# Schematic.net
KiCad netlist of a schematic drawn in EAGLE
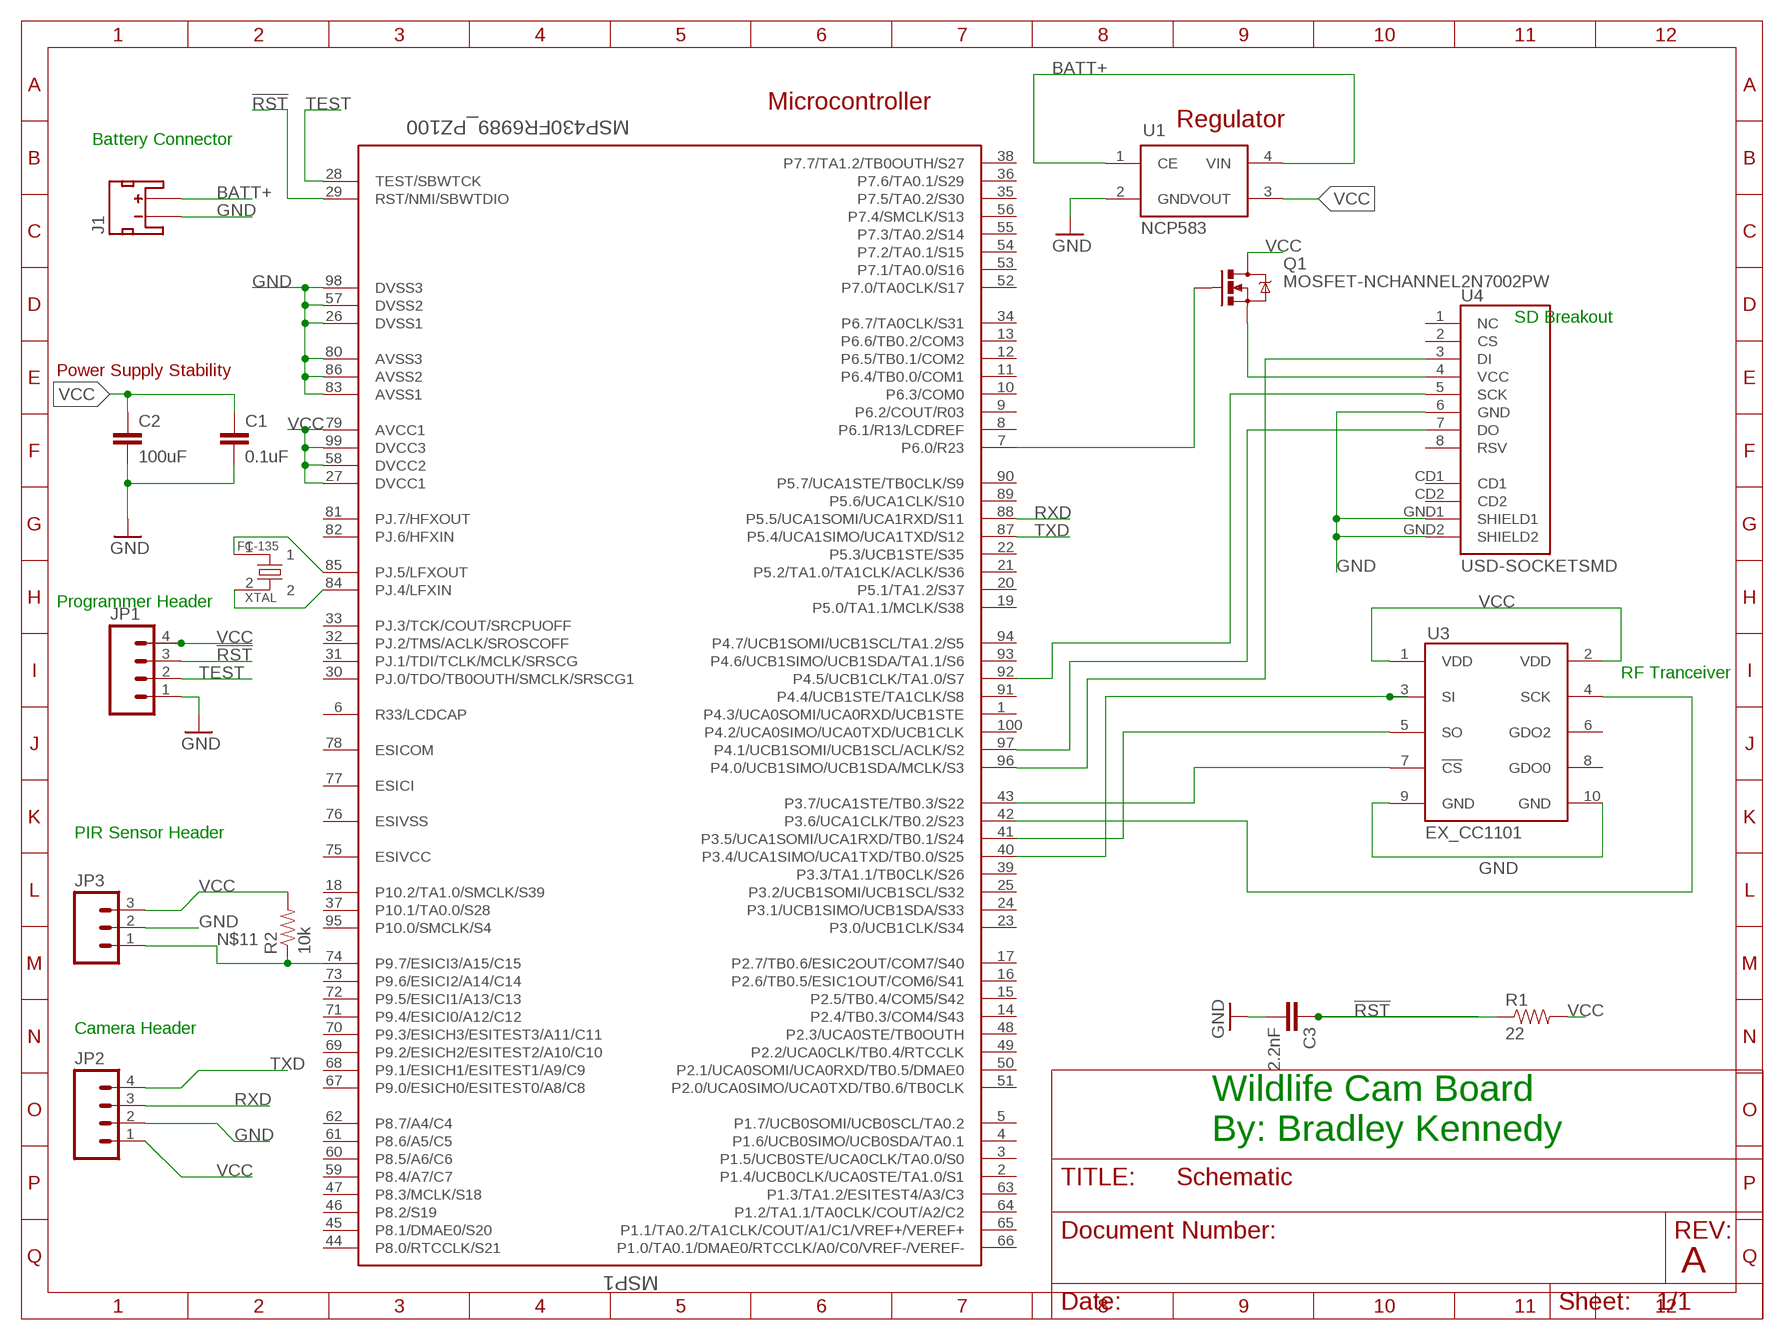
[diagram p0: schematic, sheet 1]

(export (version "E")
  (design (tool "Eeschema 10.0.6"))
  (components
    (comp (ref "C1")
      (value "0.1uF")
      (footprint "eagle-import:0805")
      (libsource (lib "eagle-import") (part "1.0UF-25V-+80/-20(0805)"))
    )
    (comp (ref "C2")
      (value "100uF")
      (footprint "eagle-import:0805")
      (libsource (lib "eagle-import") (part "1.0UF-25V-+80/-20(0805)"))
    )
    (comp (ref "C3")
      (value "2.2nF")
      (footprint "eagle-import:0805")
      (libsource (lib "eagle-import") (part "1.0UF-25V-+80/-20(0805)"))
    )
    (comp (ref "J1")
      (value "JST_2MM_MALE")
      (footprint "eagle-import:JST-2-SMD")
      (libsource (lib "eagle-import") (part "JST_2MM_MALE"))
    )
    (comp (ref "JP1")
      (value "M04PTH")
      (footprint "eagle-import:1X04")
      (libsource (lib "eagle-import") (part "M04PTH"))
    )
    (comp (ref "JP2")
      (value "M04PTH")
      (footprint "eagle-import:1X04")
      (libsource (lib "eagle-import") (part "M04PTH"))
    )
    (comp (ref "JP3")
      (value "M03PTH")
      (footprint "eagle-import:1X03")
      (libsource (lib "eagle-import") (part "M03PTH"))
    )
    (comp (ref "MSP1")
      (value "MSP430FR6989_PZ100")
      (footprint "eagle-import:PZ100")
      (libsource (lib "eagle-import") (part "MSP430FR6989_PZ100"))
    )
    (comp (ref "Q1")
      (value "MOSFET-NCHANNEL2N7002PW")
      (footprint "eagle-import:SOT323")
      (libsource (lib "eagle-import") (part "MOSFET-NCHANNEL2N7002PW"))
    )
    (comp (ref "R1")
      (value "22")
      (footprint "eagle-import:0603-RES")
      (libsource (lib "eagle-import") (part "22OHM1/10W1%(0603)"))
    )
    (comp (ref "R2")
      (value "10k")
      (footprint "eagle-import:AXIAL-0.3EZ")
      (libsource (lib "eagle-import") (part "10KOHM-1/4W-1%(PTH)HORIZ-KIT"))
    )
    (comp (ref "U1")
      (value "NCP583")
      (footprint "eagle-import:SC82-AB_1PRIMARY")
      (libsource (lib "eagle-import") (part "NCP583"))
    )
    (comp (ref "U3")
      (value "EX_CC1101")
      (footprint "eagle-import:2X5")
      (libsource (lib "eagle-import") (part "EX_CC1101"))
    )
    (comp (ref "U4")
      (value "USD-SOCKETSMD")
      (footprint "eagle-import:MICRO-SD-SOCKET-PP")
      (libsource (lib "eagle-import") (part "USD-SOCKETSMD"))
    )
    (comp (ref "XTAL")
      (value "FC-135")
      (footprint "eagle-import:FC-135_1PRIMARY")
      (libsource (lib "eagle-import") (part "FC-135"))
    )
  )
  (nets
    (net (code "1") (name "/BATT+") (class "Default")
      (node (ref "J1") (pin "2") (pinfunction "+_2") (pintype "bidirectional"))
      (node (ref "U1") (pin "1") (pinfunction "CE_1") (pintype "bidirectional"))
      (node (ref "U1") (pin "4") (pinfunction "VIN_4") (pintype "bidirectional"))
    )
    (net (code "2") (name "/N$11") (class "Default")
      (node (ref "JP3") (pin "1") (pinfunction "1_1") (pintype "passive"))
      (node (ref "MSP1") (pin "74") (pinfunction "P9.7/ESICI3/A15/C15_74") (pintype "bidirectional"))
      (node (ref "R2") (pin "P$1") (pinfunction "1_P$1") (pintype "passive"))
    )
    (net (code "3") (name "/RXD") (class "Default")
      (node (ref "JP2") (pin "3") (pinfunction "3_3") (pintype "passive"))
      (node (ref "MSP1") (pin "88") (pinfunction "P5.5/UCA1SOMI/UCA1RXD/S11_88") (pintype "bidirectional"))
    )
    (net (code "4") (name "/TEST") (class "Default")
      (node (ref "JP1") (pin "2") (pinfunction "2_2") (pintype "passive"))
      (node (ref "MSP1") (pin "28") (pinfunction "TEST/SBWTCK_28") (pintype "bidirectional"))
    )
    (net (code "5") (name "/TXD") (class "Default")
      (node (ref "JP2") (pin "4") (pinfunction "4_4") (pintype "passive"))
      (node (ref "MSP1") (pin "87") (pinfunction "P5.4/UCA1SIMO/UCA1TXD/S12_87") (pintype "bidirectional"))
    )
    (net (code "6") (name "/~{RST}") (class "Default")
      (node (ref "C3") (pin "1") (pinfunction "1_1") (pintype "passive"))
      (node (ref "JP1") (pin "3") (pinfunction "3_3") (pintype "passive"))
      (node (ref "MSP1") (pin "29") (pinfunction "RST/NMI/SBWTDIO_29") (pintype "bidirectional"))
      (node (ref "R1") (pin "1") (pinfunction "1_1") (pintype "passive"))
    )
    (net (code "7") (name "GND") (class "Default")
      (node (ref "C1") (pin "2") (pinfunction "2_2") (pintype "passive"))
      (node (ref "C2") (pin "2") (pinfunction "2_2") (pintype "passive"))
      (node (ref "C3") (pin "2") (pinfunction "2_2") (pintype "passive"))
      (node (ref "J1") (pin "1") (pinfunction "-_1") (pintype "bidirectional"))
      (node (ref "JP1") (pin "1") (pinfunction "1_1") (pintype "passive"))
      (node (ref "JP2") (pin "2") (pinfunction "2_2") (pintype "passive"))
      (node (ref "JP3") (pin "2") (pinfunction "2_2") (pintype "passive"))
      (node (ref "MSP1") (pin "26") (pinfunction "DVSS1_26") (pintype "bidirectional"))
      (node (ref "MSP1") (pin "57") (pinfunction "DVSS2_57") (pintype "bidirectional"))
      (node (ref "MSP1") (pin "80") (pinfunction "AVSS3_80") (pintype "bidirectional"))
      (node (ref "MSP1") (pin "83") (pinfunction "AVSS1_83") (pintype "bidirectional"))
      (node (ref "MSP1") (pin "86") (pinfunction "AVSS2_86") (pintype "bidirectional"))
      (node (ref "MSP1") (pin "98") (pinfunction "DVSS3_98") (pintype "bidirectional"))
      (node (ref "U1") (pin "2") (pinfunction "GND_2") (pintype "bidirectional"))
      (node (ref "U3") (pin "10") (pinfunction "GND_10") (pintype "bidirectional"))
      (node (ref "U3") (pin "9") (pinfunction "GND_9") (pintype "bidirectional"))
      (node (ref "U4") (pin "6") (pinfunction "GND_6") (pintype "bidirectional"))
      (node (ref "U4") (pin "GND1") (pinfunction "SHIELD1_GND1") (pintype "bidirectional"))
      (node (ref "U4") (pin "GND2") (pinfunction "SHIELD2_GND2") (pintype "bidirectional"))
    )
    (net (code "8") (name "Net-(MSP1-P3.4{slash}UCA1SIMO{slash}UCA1TXD{slash}TB0.0{slash}S25)") (class "Default")
      (node (ref "MSP1") (pin "40") (pinfunction "P3.4/UCA1SIMO/UCA1TXD/TB0.0/S25_40") (pintype "bidirectional"))
      (node (ref "U3") (pin "3") (pinfunction "SI_3") (pintype "bidirectional"))
    )
    (net (code "9") (name "Net-(MSP1-P3.5{slash}UCA1SOMI{slash}UCA1RXD{slash}TB0.1{slash}S24)") (class "Default")
      (node (ref "MSP1") (pin "41") (pinfunction "P3.5/UCA1SOMI/UCA1RXD/TB0.1/S24_41") (pintype "bidirectional"))
      (node (ref "U3") (pin "5") (pinfunction "SO_5") (pintype "bidirectional"))
    )
    (net (code "10") (name "Net-(MSP1-P3.6{slash}UCA1CLK{slash}TB0.2{slash}S23)") (class "Default")
      (node (ref "MSP1") (pin "42") (pinfunction "P3.6/UCA1CLK/TB0.2/S23_42") (pintype "bidirectional"))
      (node (ref "U3") (pin "4") (pinfunction "SCK_4") (pintype "bidirectional"))
    )
    (net (code "11") (name "Net-(MSP1-P3.7{slash}UCA1STE{slash}TB0.3{slash}S22)") (class "Default")
      (node (ref "MSP1") (pin "43") (pinfunction "P3.7/UCA1STE/TB0.3/S22_43") (pintype "bidirectional"))
      (node (ref "U3") (pin "7") (pinfunction "~{CS}_7") (pintype "bidirectional"))
    )
    (net (code "12") (name "Net-(MSP1-P4.0{slash}UCB1SIMO{slash}UCB1SDA{slash}MCLK{slash}S3)") (class "Default")
      (node (ref "MSP1") (pin "96") (pinfunction "P4.0/UCB1SIMO/UCB1SDA/MCLK/S3_96") (pintype "bidirectional"))
      (node (ref "U4") (pin "3") (pinfunction "DI_3") (pintype "bidirectional"))
    )
    (net (code "13") (name "Net-(MSP1-P4.1{slash}UCB1SOMI{slash}UCB1SCL{slash}ACLK{slash}S2)") (class "Default")
      (node (ref "MSP1") (pin "97") (pinfunction "P4.1/UCB1SOMI/UCB1SCL/ACLK/S2_97") (pintype "bidirectional"))
      (node (ref "U4") (pin "7") (pinfunction "DO_7") (pintype "bidirectional"))
    )
    (net (code "14") (name "Net-(MSP1-P4.5{slash}UCB1CLK{slash}TA1.0{slash}S7)") (class "Default")
      (node (ref "MSP1") (pin "92") (pinfunction "P4.5/UCB1CLK/TA1.0/S7_92") (pintype "bidirectional"))
      (node (ref "U4") (pin "5") (pinfunction "SCK_5") (pintype "bidirectional"))
    )
    (net (code "15") (name "Net-(MSP1-P6.0{slash}R23)") (class "Default")
      (node (ref "MSP1") (pin "7") (pinfunction "P6.0/R23_7") (pintype "bidirectional"))
      (node (ref "Q1") (pin "1") (pinfunction "G_1") (pintype "passive"))
    )
    (net (code "16") (name "Net-(MSP1-PJ.4{slash}LFXIN)") (class "Default")
      (node (ref "MSP1") (pin "84") (pinfunction "PJ.4/LFXIN_84") (pintype "bidirectional"))
      (node (ref "XTAL") (pin "2") (pinfunction "2_2") (pintype "bidirectional"))
    )
    (net (code "17") (name "Net-(MSP1-PJ.5{slash}LFXOUT)") (class "Default")
      (node (ref "MSP1") (pin "85") (pinfunction "PJ.5/LFXOUT_85") (pintype "bidirectional"))
      (node (ref "XTAL") (pin "1") (pinfunction "1_1") (pintype "bidirectional"))
    )
    (net (code "18") (name "Net-(Q1-S)") (class "Default")
      (node (ref "Q1") (pin "2") (pinfunction "S_2") (pintype "passive"))
      (node (ref "U4") (pin "4") (pinfunction "VCC_4") (pintype "bidirectional"))
    )
    (net (code "19") (name "VCC") (class "Default")
      (node (ref "C1") (pin "1") (pinfunction "1_1") (pintype "passive"))
      (node (ref "C2") (pin "1") (pinfunction "1_1") (pintype "passive"))
      (node (ref "JP1") (pin "4") (pinfunction "4_4") (pintype "passive"))
      (node (ref "JP2") (pin "1") (pinfunction "1_1") (pintype "passive"))
      (node (ref "JP3") (pin "3") (pinfunction "3_3") (pintype "passive"))
      (node (ref "MSP1") (pin "27") (pinfunction "DVCC1_27") (pintype "bidirectional"))
      (node (ref "MSP1") (pin "58") (pinfunction "DVCC2_58") (pintype "bidirectional"))
      (node (ref "MSP1") (pin "79") (pinfunction "AVCC1_79") (pintype "bidirectional"))
      (node (ref "MSP1") (pin "99") (pinfunction "DVCC3_99") (pintype "bidirectional"))
      (node (ref "Q1") (pin "3") (pinfunction "D_3") (pintype "passive"))
      (node (ref "R1") (pin "2") (pinfunction "2_2") (pintype "passive"))
      (node (ref "R2") (pin "P$2") (pinfunction "2_P$2") (pintype "passive"))
      (node (ref "U1") (pin "3") (pinfunction "VOUT_3") (pintype "bidirectional"))
      (node (ref "U3") (pin "1") (pinfunction "VDD_1") (pintype "bidirectional"))
      (node (ref "U3") (pin "2") (pinfunction "VDD_2") (pintype "bidirectional"))
    )
    (net (code "20") (name "unconnected-(J1-PAD1-PadNC1)") (class "Default")
      (node (ref "J1") (pin "NC1") (pinfunction "PAD1_NC1") (pintype "bidirectional"))
    )
    (net (code "21") (name "unconnected-(J1-PAD2-PadNC2)") (class "Default")
      (node (ref "J1") (pin "NC2") (pinfunction "PAD2_NC2") (pintype "bidirectional"))
    )
    (net (code "22") (name "unconnected-(MSP1-ESICI-Pad77)") (class "Default")
      (node (ref "MSP1") (pin "77") (pinfunction "ESICI_77") (pintype "bidirectional"))
    )
    (net (code "23") (name "unconnected-(MSP1-ESICOM-Pad78)") (class "Default")
      (node (ref "MSP1") (pin "78") (pinfunction "ESICOM_78") (pintype "bidirectional"))
    )
    (net (code "24") (name "unconnected-(MSP1-ESIVCC-Pad75)") (class "Default")
      (node (ref "MSP1") (pin "75") (pinfunction "ESIVCC_75") (pintype "bidirectional"))
    )
    (net (code "25") (name "unconnected-(MSP1-ESIVSS-Pad76)") (class "Default")
      (node (ref "MSP1") (pin "76") (pinfunction "ESIVSS_76") (pintype "bidirectional"))
    )
    (net (code "26") (name "unconnected-(MSP1-P1.0{slash}TA0.1{slash}DMAE0{slash}RTCCLK{slash}A0{slash}C0{slash}VREF-{slash}VEREF--Pad66)") (class "Default")
      (node (ref "MSP1") (pin "66") (pinfunction "P1.0/TA0.1/DMAE0/RTCCLK/A0/C0/VREF-/VEREF-_66") (pintype "bidirectional"))
    )
    (net (code "27") (name "unconnected-(MSP1-P1.1{slash}TA0.2{slash}TA1CLK{slash}COUT{slash}A1{slash}C1{slash}VREF+{slash}VEREF+-Pad65)") (class "Default")
      (node (ref "MSP1") (pin "65") (pinfunction "P1.1/TA0.2/TA1CLK/COUT/A1/C1/VREF+/VEREF+_65") (pintype "bidirectional"))
    )
    (net (code "28") (name "unconnected-(MSP1-P1.2{slash}TA1.1{slash}TA0CLK{slash}COUT{slash}A2{slash}C2-Pad64)") (class "Default")
      (node (ref "MSP1") (pin "64") (pinfunction "P1.2/TA1.1/TA0CLK/COUT/A2/C2_64") (pintype "bidirectional"))
    )
    (net (code "29") (name "unconnected-(MSP1-P1.3{slash}TA1.2{slash}ESITEST4{slash}A3{slash}C3-Pad63)") (class "Default")
      (node (ref "MSP1") (pin "63") (pinfunction "P1.3/TA1.2/ESITEST4/A3/C3_63") (pintype "bidirectional"))
    )
    (net (code "30") (name "unconnected-(MSP1-P1.4{slash}UCB0CLK{slash}UCA0STE{slash}TA1.0{slash}S1-Pad2)") (class "Default")
      (node (ref "MSP1") (pin "2") (pinfunction "P1.4/UCB0CLK/UCA0STE/TA1.0/S1_2") (pintype "bidirectional"))
    )
    (net (code "31") (name "unconnected-(MSP1-P1.5{slash}UCB0STE{slash}UCA0CLK{slash}TA0.0{slash}S0-Pad3)") (class "Default")
      (node (ref "MSP1") (pin "3") (pinfunction "P1.5/UCB0STE/UCA0CLK/TA0.0/S0_3") (pintype "bidirectional"))
    )
    (net (code "32") (name "unconnected-(MSP1-P1.6{slash}UCB0SIMO{slash}UCB0SDA{slash}TA0.1-Pad4)") (class "Default")
      (node (ref "MSP1") (pin "4") (pinfunction "P1.6/UCB0SIMO/UCB0SDA/TA0.1_4") (pintype "bidirectional"))
    )
    (net (code "33") (name "unconnected-(MSP1-P1.7{slash}UCB0SOMI{slash}UCB0SCL{slash}TA0.2-Pad5)") (class "Default")
      (node (ref "MSP1") (pin "5") (pinfunction "P1.7/UCB0SOMI/UCB0SCL/TA0.2_5") (pintype "bidirectional"))
    )
    (net (code "34") (name "unconnected-(MSP1-P2.0{slash}UCA0SIMO{slash}UCA0TXD{slash}TB0.6{slash}TB0CLK-Pad51)") (class "Default")
      (node (ref "MSP1") (pin "51") (pinfunction "P2.0/UCA0SIMO/UCA0TXD/TB0.6/TB0CLK_51") (pintype "bidirectional"))
    )
    (net (code "35") (name "unconnected-(MSP1-P2.1{slash}UCA0SOMI{slash}UCA0RXD{slash}TB0.5{slash}DMAE0-Pad50)") (class "Default")
      (node (ref "MSP1") (pin "50") (pinfunction "P2.1/UCA0SOMI/UCA0RXD/TB0.5/DMAE0_50") (pintype "bidirectional"))
    )
    (net (code "36") (name "unconnected-(MSP1-P2.2{slash}UCA0CLK{slash}TB0.4{slash}RTCCLK-Pad49)") (class "Default")
      (node (ref "MSP1") (pin "49") (pinfunction "P2.2/UCA0CLK/TB0.4/RTCCLK_49") (pintype "bidirectional"))
    )
    (net (code "37") (name "unconnected-(MSP1-P2.3{slash}UCA0STE{slash}TB0OUTH-Pad48)") (class "Default")
      (node (ref "MSP1") (pin "48") (pinfunction "P2.3/UCA0STE/TB0OUTH_48") (pintype "bidirectional"))
    )
    (net (code "38") (name "unconnected-(MSP1-P2.4{slash}TB0.3{slash}COM4{slash}S43-Pad14)") (class "Default")
      (node (ref "MSP1") (pin "14") (pinfunction "P2.4/TB0.3/COM4/S43_14") (pintype "bidirectional"))
    )
    (net (code "39") (name "unconnected-(MSP1-P2.5{slash}TB0.4{slash}COM5{slash}S42-Pad15)") (class "Default")
      (node (ref "MSP1") (pin "15") (pinfunction "P2.5/TB0.4/COM5/S42_15") (pintype "bidirectional"))
    )
    (net (code "40") (name "unconnected-(MSP1-P2.6{slash}TB0.5{slash}ESIC1OUT{slash}COM6{slash}S41-Pad16)") (class "Default")
      (node (ref "MSP1") (pin "16") (pinfunction "P2.6/TB0.5/ESIC1OUT/COM6/S41_16") (pintype "bidirectional"))
    )
    (net (code "41") (name "unconnected-(MSP1-P2.7{slash}TB0.6{slash}ESIC2OUT{slash}COM7{slash}S40-Pad17)") (class "Default")
      (node (ref "MSP1") (pin "17") (pinfunction "P2.7/TB0.6/ESIC2OUT/COM7/S40_17") (pintype "bidirectional"))
    )
    (net (code "42") (name "unconnected-(MSP1-P3.0{slash}UCB1CLK{slash}S34-Pad23)") (class "Default")
      (node (ref "MSP1") (pin "23") (pinfunction "P3.0/UCB1CLK/S34_23") (pintype "bidirectional"))
    )
    (net (code "43") (name "unconnected-(MSP1-P3.1{slash}UCB1SIMO{slash}UCB1SDA{slash}S33-Pad24)") (class "Default")
      (node (ref "MSP1") (pin "24") (pinfunction "P3.1/UCB1SIMO/UCB1SDA/S33_24") (pintype "bidirectional"))
    )
    (net (code "44") (name "unconnected-(MSP1-P3.2{slash}UCB1SOMI{slash}UCB1SCL{slash}S32-Pad25)") (class "Default")
      (node (ref "MSP1") (pin "25") (pinfunction "P3.2/UCB1SOMI/UCB1SCL/S32_25") (pintype "bidirectional"))
    )
    (net (code "45") (name "unconnected-(MSP1-P3.3{slash}TA1.1{slash}TB0CLK{slash}S26-Pad39)") (class "Default")
      (node (ref "MSP1") (pin "39") (pinfunction "P3.3/TA1.1/TB0CLK/S26_39") (pintype "bidirectional"))
    )
    (net (code "46") (name "unconnected-(MSP1-P4.2{slash}UCA0SIMO{slash}UCA0TXD{slash}UCB1CLK-Pad100)") (class "Default")
      (node (ref "MSP1") (pin "100") (pinfunction "P4.2/UCA0SIMO/UCA0TXD/UCB1CLK_100") (pintype "bidirectional"))
    )
    (net (code "47") (name "unconnected-(MSP1-P4.3{slash}UCA0SOMI{slash}UCA0RXD{slash}UCB1STE-Pad1)") (class "Default")
      (node (ref "MSP1") (pin "1") (pinfunction "P4.3/UCA0SOMI/UCA0RXD/UCB1STE_1") (pintype "bidirectional"))
    )
    (net (code "48") (name "unconnected-(MSP1-P4.4{slash}UCB1STE{slash}TA1CLK{slash}S8-Pad91)") (class "Default")
      (node (ref "MSP1") (pin "91") (pinfunction "P4.4/UCB1STE/TA1CLK/S8_91") (pintype "bidirectional"))
    )
    (net (code "49") (name "unconnected-(MSP1-P4.6{slash}UCB1SIMO{slash}UCB1SDA{slash}TA1.1{slash}S6-Pad93)") (class "Default")
      (node (ref "MSP1") (pin "93") (pinfunction "P4.6/UCB1SIMO/UCB1SDA/TA1.1/S6_93") (pintype "bidirectional"))
    )
    (net (code "50") (name "unconnected-(MSP1-P4.7{slash}UCB1SOMI{slash}UCB1SCL{slash}TA1.2{slash}S5-Pad94)") (class "Default")
      (node (ref "MSP1") (pin "94") (pinfunction "P4.7/UCB1SOMI/UCB1SCL/TA1.2/S5_94") (pintype "bidirectional"))
    )
    (net (code "51") (name "unconnected-(MSP1-P5.0{slash}TA1.1{slash}MCLK{slash}S38-Pad19)") (class "Default")
      (node (ref "MSP1") (pin "19") (pinfunction "P5.0/TA1.1/MCLK/S38_19") (pintype "bidirectional"))
    )
    (net (code "52") (name "unconnected-(MSP1-P5.1{slash}TA1.2{slash}S37-Pad20)") (class "Default")
      (node (ref "MSP1") (pin "20") (pinfunction "P5.1/TA1.2/S37_20") (pintype "bidirectional"))
    )
    (net (code "53") (name "unconnected-(MSP1-P5.2{slash}TA1.0{slash}TA1CLK{slash}ACLK{slash}S36-Pad21)") (class "Default")
      (node (ref "MSP1") (pin "21") (pinfunction "P5.2/TA1.0/TA1CLK/ACLK/S36_21") (pintype "bidirectional"))
    )
    (net (code "54") (name "unconnected-(MSP1-P5.3{slash}UCB1STE{slash}S35-Pad22)") (class "Default")
      (node (ref "MSP1") (pin "22") (pinfunction "P5.3/UCB1STE/S35_22") (pintype "bidirectional"))
    )
    (net (code "55") (name "unconnected-(MSP1-P5.6{slash}UCA1CLK{slash}S10-Pad89)") (class "Default")
      (node (ref "MSP1") (pin "89") (pinfunction "P5.6/UCA1CLK/S10_89") (pintype "bidirectional"))
    )
    (net (code "56") (name "unconnected-(MSP1-P5.7{slash}UCA1STE{slash}TB0CLK{slash}S9-Pad90)") (class "Default")
      (node (ref "MSP1") (pin "90") (pinfunction "P5.7/UCA1STE/TB0CLK/S9_90") (pintype "bidirectional"))
    )
    (net (code "57") (name "unconnected-(MSP1-P6.1{slash}R13{slash}LCDREF-Pad8)") (class "Default")
      (node (ref "MSP1") (pin "8") (pinfunction "P6.1/R13/LCDREF_8") (pintype "bidirectional"))
    )
    (net (code "58") (name "unconnected-(MSP1-P6.2{slash}COUT{slash}R03-Pad9)") (class "Default")
      (node (ref "MSP1") (pin "9") (pinfunction "P6.2/COUT/R03_9") (pintype "bidirectional"))
    )
    (net (code "59") (name "unconnected-(MSP1-P6.3{slash}COM0-Pad10)") (class "Default")
      (node (ref "MSP1") (pin "10") (pinfunction "P6.3/COM0_10") (pintype "bidirectional"))
    )
    (net (code "60") (name "unconnected-(MSP1-P6.4{slash}TB0.0{slash}COM1-Pad11)") (class "Default")
      (node (ref "MSP1") (pin "11") (pinfunction "P6.4/TB0.0/COM1_11") (pintype "bidirectional"))
    )
    (net (code "61") (name "unconnected-(MSP1-P6.5{slash}TB0.1{slash}COM2-Pad12)") (class "Default")
      (node (ref "MSP1") (pin "12") (pinfunction "P6.5/TB0.1/COM2_12") (pintype "bidirectional"))
    )
    (net (code "62") (name "unconnected-(MSP1-P6.6{slash}TB0.2{slash}COM3-Pad13)") (class "Default")
      (node (ref "MSP1") (pin "13") (pinfunction "P6.6/TB0.2/COM3_13") (pintype "bidirectional"))
    )
    (net (code "63") (name "unconnected-(MSP1-P6.7{slash}TA0CLK{slash}S31-Pad34)") (class "Default")
      (node (ref "MSP1") (pin "34") (pinfunction "P6.7/TA0CLK/S31_34") (pintype "bidirectional"))
    )
    (net (code "64") (name "unconnected-(MSP1-P7.0{slash}TA0CLK{slash}S17-Pad52)") (class "Default")
      (node (ref "MSP1") (pin "52") (pinfunction "P7.0/TA0CLK/S17_52") (pintype "bidirectional"))
    )
    (net (code "65") (name "unconnected-(MSP1-P7.1{slash}TA0.0{slash}S16-Pad53)") (class "Default")
      (node (ref "MSP1") (pin "53") (pinfunction "P7.1/TA0.0/S16_53") (pintype "bidirectional"))
    )
    (net (code "66") (name "unconnected-(MSP1-P7.2{slash}TA0.1{slash}S15-Pad54)") (class "Default")
      (node (ref "MSP1") (pin "54") (pinfunction "P7.2/TA0.1/S15_54") (pintype "bidirectional"))
    )
    (net (code "67") (name "unconnected-(MSP1-P7.3{slash}TA0.2{slash}S14-Pad55)") (class "Default")
      (node (ref "MSP1") (pin "55") (pinfunction "P7.3/TA0.2/S14_55") (pintype "bidirectional"))
    )
    (net (code "68") (name "unconnected-(MSP1-P7.4{slash}SMCLK{slash}S13-Pad56)") (class "Default")
      (node (ref "MSP1") (pin "56") (pinfunction "P7.4/SMCLK/S13_56") (pintype "bidirectional"))
    )
    (net (code "69") (name "unconnected-(MSP1-P7.5{slash}TA0.2{slash}S30-Pad35)") (class "Default")
      (node (ref "MSP1") (pin "35") (pinfunction "P7.5/TA0.2/S30_35") (pintype "bidirectional"))
    )
    (net (code "70") (name "unconnected-(MSP1-P7.6{slash}TA0.1{slash}S29-Pad36)") (class "Default")
      (node (ref "MSP1") (pin "36") (pinfunction "P7.6/TA0.1/S29_36") (pintype "bidirectional"))
    )
    (net (code "71") (name "unconnected-(MSP1-P7.7{slash}TA1.2{slash}TB0OUTH{slash}S27-Pad38)") (class "Default")
      (node (ref "MSP1") (pin "38") (pinfunction "P7.7/TA1.2/TB0OUTH/S27_38") (pintype "bidirectional"))
    )
    (net (code "72") (name "unconnected-(MSP1-P8.0{slash}RTCCLK{slash}S21-Pad44)") (class "Default")
      (node (ref "MSP1") (pin "44") (pinfunction "P8.0/RTCCLK/S21_44") (pintype "bidirectional"))
    )
    (net (code "73") (name "unconnected-(MSP1-P8.1{slash}DMAE0{slash}S20-Pad45)") (class "Default")
      (node (ref "MSP1") (pin "45") (pinfunction "P8.1/DMAE0/S20_45") (pintype "bidirectional"))
    )
    (net (code "74") (name "unconnected-(MSP1-P8.2{slash}S19-Pad46)") (class "Default")
      (node (ref "MSP1") (pin "46") (pinfunction "P8.2/S19_46") (pintype "bidirectional"))
    )
    (net (code "75") (name "unconnected-(MSP1-P8.3{slash}MCLK{slash}S18-Pad47)") (class "Default")
      (node (ref "MSP1") (pin "47") (pinfunction "P8.3/MCLK/S18_47") (pintype "bidirectional"))
    )
    (net (code "76") (name "unconnected-(MSP1-P8.4{slash}A7{slash}C7-Pad59)") (class "Default")
      (node (ref "MSP1") (pin "59") (pinfunction "P8.4/A7/C7_59") (pintype "bidirectional"))
    )
    (net (code "77") (name "unconnected-(MSP1-P8.5{slash}A6{slash}C6-Pad60)") (class "Default")
      (node (ref "MSP1") (pin "60") (pinfunction "P8.5/A6/C6_60") (pintype "bidirectional"))
    )
    (net (code "78") (name "unconnected-(MSP1-P8.6{slash}A5{slash}C5-Pad61)") (class "Default")
      (node (ref "MSP1") (pin "61") (pinfunction "P8.6/A5/C5_61") (pintype "bidirectional"))
    )
    (net (code "79") (name "unconnected-(MSP1-P8.7{slash}A4{slash}C4-Pad62)") (class "Default")
      (node (ref "MSP1") (pin "62") (pinfunction "P8.7/A4/C4_62") (pintype "bidirectional"))
    )
    (net (code "80") (name "unconnected-(MSP1-P9.0{slash}ESICH0{slash}ESITEST0{slash}A8{slash}C8-Pad67)") (class "Default")
      (node (ref "MSP1") (pin "67") (pinfunction "P9.0/ESICH0/ESITEST0/A8/C8_67") (pintype "bidirectional"))
    )
    (net (code "81") (name "unconnected-(MSP1-P9.1{slash}ESICH1{slash}ESITEST1{slash}A9{slash}C9-Pad68)") (class "Default")
      (node (ref "MSP1") (pin "68") (pinfunction "P9.1/ESICH1/ESITEST1/A9/C9_68") (pintype "bidirectional"))
    )
    (net (code "82") (name "unconnected-(MSP1-P9.2{slash}ESICH2{slash}ESITEST2{slash}A10{slash}C10-Pad69)") (class "Default")
      (node (ref "MSP1") (pin "69") (pinfunction "P9.2/ESICH2/ESITEST2/A10/C10_69") (pintype "bidirectional"))
    )
    (net (code "83") (name "unconnected-(MSP1-P9.3{slash}ESICH3{slash}ESITEST3{slash}A11{slash}C11-Pad70)") (class "Default")
      (node (ref "MSP1") (pin "70") (pinfunction "P9.3/ESICH3/ESITEST3/A11/C11_70") (pintype "bidirectional"))
    )
    (net (code "84") (name "unconnected-(MSP1-P9.4{slash}ESICI0{slash}A12{slash}C12-Pad71)") (class "Default")
      (node (ref "MSP1") (pin "71") (pinfunction "P9.4/ESICI0/A12/C12_71") (pintype "bidirectional"))
    )
    (net (code "85") (name "unconnected-(MSP1-P9.5{slash}ESICI1{slash}A13{slash}C13-Pad72)") (class "Default")
      (node (ref "MSP1") (pin "72") (pinfunction "P9.5/ESICI1/A13/C13_72") (pintype "bidirectional"))
    )
    (net (code "86") (name "unconnected-(MSP1-P9.6{slash}ESICI2{slash}A14{slash}C14-Pad73)") (class "Default")
      (node (ref "MSP1") (pin "73") (pinfunction "P9.6/ESICI2/A14/C14_73") (pintype "bidirectional"))
    )
    (net (code "87") (name "unconnected-(MSP1-P10.0{slash}SMCLK{slash}S4-Pad95)") (class "Default")
      (node (ref "MSP1") (pin "95") (pinfunction "P10.0/SMCLK/S4_95") (pintype "bidirectional"))
    )
    (net (code "88") (name "unconnected-(MSP1-P10.1{slash}TA0.0{slash}S28-Pad37)") (class "Default")
      (node (ref "MSP1") (pin "37") (pinfunction "P10.1/TA0.0/S28_37") (pintype "bidirectional"))
    )
    (net (code "89") (name "unconnected-(MSP1-P10.2{slash}TA1.0{slash}SMCLK{slash}S39-Pad18)") (class "Default")
      (node (ref "MSP1") (pin "18") (pinfunction "P10.2/TA1.0/SMCLK/S39_18") (pintype "bidirectional"))
    )
    (net (code "90") (name "unconnected-(MSP1-PJ.0{slash}TDO{slash}TB0OUTH{slash}SMCLK{slash}SRSCG1-Pad30)") (class "Default")
      (node (ref "MSP1") (pin "30") (pinfunction "PJ.0/TDO/TB0OUTH/SMCLK/SRSCG1_30") (pintype "bidirectional"))
    )
    (net (code "91") (name "unconnected-(MSP1-PJ.1{slash}TDI{slash}TCLK{slash}MCLK{slash}SRSCG-Pad31)") (class "Default")
      (node (ref "MSP1") (pin "31") (pinfunction "PJ.1/TDI/TCLK/MCLK/SRSCG_31") (pintype "bidirectional"))
    )
    (net (code "92") (name "unconnected-(MSP1-PJ.2{slash}TMS{slash}ACLK{slash}SROSCOFF-Pad32)") (class "Default")
      (node (ref "MSP1") (pin "32") (pinfunction "PJ.2/TMS/ACLK/SROSCOFF_32") (pintype "bidirectional"))
    )
    (net (code "93") (name "unconnected-(MSP1-PJ.3{slash}TCK{slash}COUT{slash}SRCPUOFF-Pad33)") (class "Default")
      (node (ref "MSP1") (pin "33") (pinfunction "PJ.3/TCK/COUT/SRCPUOFF_33") (pintype "bidirectional"))
    )
    (net (code "94") (name "unconnected-(MSP1-PJ.6{slash}HFXIN-Pad82)") (class "Default")
      (node (ref "MSP1") (pin "82") (pinfunction "PJ.6/HFXIN_82") (pintype "bidirectional"))
    )
    (net (code "95") (name "unconnected-(MSP1-PJ.7{slash}HFXOUT-Pad81)") (class "Default")
      (node (ref "MSP1") (pin "81") (pinfunction "PJ.7/HFXOUT_81") (pintype "bidirectional"))
    )
    (net (code "96") (name "unconnected-(MSP1-R33{slash}LCDCAP-Pad6)") (class "Default")
      (node (ref "MSP1") (pin "6") (pinfunction "R33/LCDCAP_6") (pintype "bidirectional"))
    )
    (net (code "97") (name "unconnected-(U3-GDO0-Pad8)") (class "Default")
      (node (ref "U3") (pin "8") (pinfunction "GDO0_8") (pintype "bidirectional"))
    )
    (net (code "98") (name "unconnected-(U3-GDO2-Pad6)") (class "Default")
      (node (ref "U3") (pin "6") (pinfunction "GDO2_6") (pintype "bidirectional"))
    )
    (net (code "99") (name "unconnected-(U4-CS-Pad2)") (class "Default")
      (node (ref "U4") (pin "2") (pinfunction "CS_2") (pintype "bidirectional"))
    )
    (net (code "100") (name "unconnected-(U4-NC-Pad1)") (class "Default")
      (node (ref "U4") (pin "1") (pinfunction "NC_1") (pintype "bidirectional"))
    )
    (net (code "101") (name "unconnected-(U4-PadCD1)") (class "Default")
      (node (ref "U4") (pin "CD1") (pinfunction "CD1_CD1") (pintype "bidirectional"))
    )
    (net (code "102") (name "unconnected-(U4-PadCD2)") (class "Default")
      (node (ref "U4") (pin "CD2") (pinfunction "CD2_CD2") (pintype "bidirectional"))
    )
    (net (code "103") (name "unconnected-(U4-RSV-Pad8)") (class "Default")
      (node (ref "U4") (pin "8") (pinfunction "RSV_8") (pintype "bidirectional"))
    )
  )
)
